# IC_74HC595.net
KiCad netlist of a schematic drawn in Altium Designer
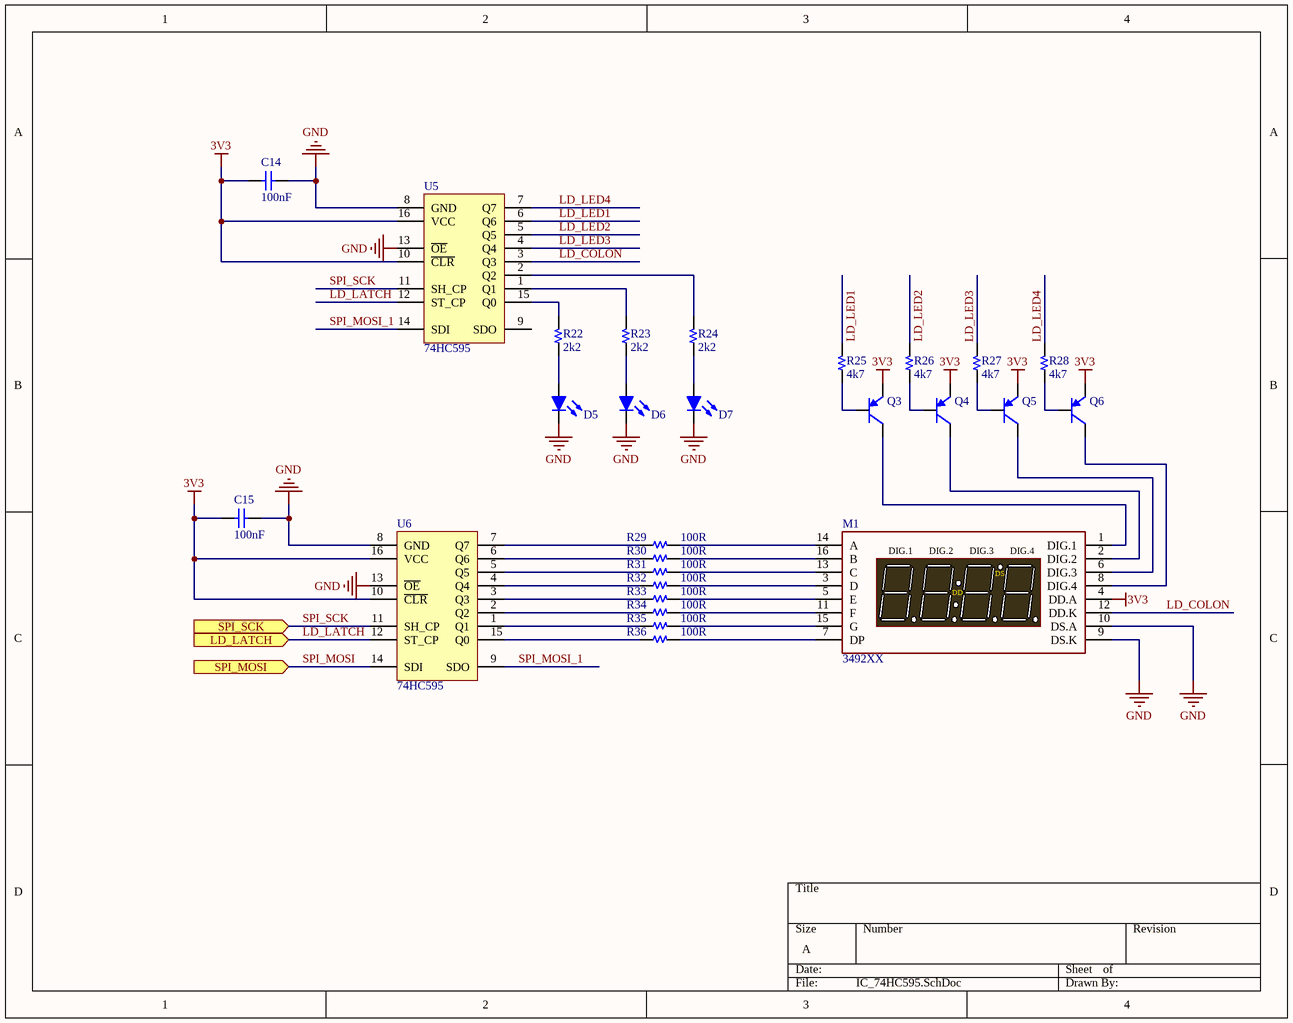
[diagram p0: IC_74HC595.SchDoc]

(export (version "E")
  (design (tool "Eeschema 10.0.6"))
  (components
    (comp (ref "C14")
      (value "100nF")
      (footprint "C 0805")
      (description "Capacitor non-pol")
      (libsource (lib "chipfc_altium_libs") (part "Capacitor NP"))
    )
    (comp (ref "C15")
      (value "100nF")
      (footprint "C 0805")
      (description "Capacitor non-pol")
      (libsource (lib "chipfc_altium_libs") (part "Capacitor NP"))
    )
    (comp (ref "D5")
      (value "Led")
      (footprint "Led 0805")
      (description "Typical LED")
      (libsource (lib "chipfc_altium_libs") (part "Led"))
    )
    (comp (ref "D6")
      (value "Led")
      (footprint "Led 0805")
      (description "Typical LED")
      (libsource (lib "chipfc_altium_libs") (part "Led"))
    )
    (comp (ref "D7")
      (value "Led")
      (footprint "Led 0805")
      (description "Typical LED")
      (libsource (lib "chipfc_altium_libs") (part "Led"))
    )
    (comp (ref "M1")
      (value "3492XX")
      (footprint "LED 7-SEG X4 3492XX")
      (description "LED 7-seg x4 HDSP-B09G")
      (libsource (lib "chipfc_altium_libs") (part "LED 7-SEG X4 3492"))
    )
    (comp (ref "Q3")
      (value "Transistor PNP")
      (footprint "SOT-23")
      (description "PNP Bipolar Transistor")
      (libsource (lib "chipfc_altium_libs") (part "Transistor PNP"))
    )
    (comp (ref "Q4")
      (value "Transistor PNP")
      (footprint "SOT-23")
      (description "PNP Bipolar Transistor")
      (libsource (lib "chipfc_altium_libs") (part "Transistor PNP"))
    )
    (comp (ref "Q5")
      (value "Transistor PNP")
      (footprint "SOT-23")
      (description "PNP Bipolar Transistor")
      (libsource (lib "chipfc_altium_libs") (part "Transistor PNP"))
    )
    (comp (ref "Q6")
      (value "Transistor PNP")
      (footprint "SOT-23")
      (description "PNP Bipolar Transistor")
      (libsource (lib "chipfc_altium_libs") (part "Transistor PNP"))
    )
    (comp (ref "R22")
      (value "2k2")
      (footprint "R 0805")
      (description "Resistor")
      (libsource (lib "chipfc_altium_libs") (part "Resistor"))
    )
    (comp (ref "R23")
      (value "2k2")
      (footprint "R 0805")
      (description "Resistor")
      (libsource (lib "chipfc_altium_libs") (part "Resistor"))
    )
    (comp (ref "R24")
      (value "2k2")
      (footprint "R 0805")
      (description "Resistor")
      (libsource (lib "chipfc_altium_libs") (part "Resistor"))
    )
    (comp (ref "R25")
      (value "4k7")
      (footprint "R 0805")
      (description "Resistor")
      (libsource (lib "chipfc_altium_libs") (part "Resistor"))
    )
    (comp (ref "R26")
      (value "4k7")
      (footprint "R 0805")
      (description "Resistor")
      (libsource (lib "chipfc_altium_libs") (part "Resistor"))
    )
    (comp (ref "R27")
      (value "4k7")
      (footprint "R 0805")
      (description "Resistor")
      (libsource (lib "chipfc_altium_libs") (part "Resistor"))
    )
    (comp (ref "R28")
      (value "4k7")
      (footprint "R 0805")
      (description "Resistor")
      (libsource (lib "chipfc_altium_libs") (part "Resistor"))
    )
    (comp (ref "R29")
      (value "100R")
      (footprint "R 0805")
      (description "Resistor")
      (libsource (lib "chipfc_altium_libs") (part "Resistor"))
    )
    (comp (ref "R30")
      (value "100R")
      (footprint "R 0805")
      (description "Resistor")
      (libsource (lib "chipfc_altium_libs") (part "Resistor"))
    )
    (comp (ref "R31")
      (value "100R")
      (footprint "R 0805")
      (description "Resistor")
      (libsource (lib "chipfc_altium_libs") (part "Resistor"))
    )
    (comp (ref "R32")
      (value "100R")
      (footprint "R 0805")
      (description "Resistor")
      (libsource (lib "chipfc_altium_libs") (part "Resistor"))
    )
    (comp (ref "R33")
      (value "100R")
      (footprint "R 0805")
      (description "Resistor")
      (libsource (lib "chipfc_altium_libs") (part "Resistor"))
    )
    (comp (ref "R34")
      (value "100R")
      (footprint "R 0805")
      (description "Resistor")
      (libsource (lib "chipfc_altium_libs") (part "Resistor"))
    )
    (comp (ref "R35")
      (value "100R")
      (footprint "R 0805")
      (description "Resistor")
      (libsource (lib "chipfc_altium_libs") (part "Resistor"))
    )
    (comp (ref "R36")
      (value "100R")
      (footprint "R 0805")
      (description "Resistor")
      (libsource (lib "chipfc_altium_libs") (part "Resistor"))
    )
    (comp (ref "U5")
      (value "74HC595")
      (footprint "SOIC-16")
      (description "8-bit serial-in, serial or parallel-out  shift register with output latches;  3-state")
      (libsource (lib "chipfc_altium_libs") (part "74HC595"))
    )
    (comp (ref "U6")
      (value "74HC595")
      (footprint "SOIC-16")
      (description "8-bit serial-in, serial or parallel-out  shift register with output latches;  3-state")
      (libsource (lib "chipfc_altium_libs") (part "74HC595"))
    )
  )
  (nets
    (net (code "1") (name "/LD_COLON") (class "Default")
      (node (ref "M1") (pin "12") (pinfunction "DD.K_12") (pintype "passive"))
      (node (ref "U5") (pin "3") (pinfunction "Q3_3") (pintype "passive"))
    )
    (net (code "2") (name "/LD_LATCH") (class "Default")
      (node (ref "U5") (pin "12") (pinfunction "ST_CP_12") (pintype "passive"))
      (node (ref "U6") (pin "12") (pinfunction "ST_CP_12") (pintype "passive"))
    )
    (net (code "3") (name "/LD_LED1") (class "Default")
      (node (ref "R25") (pin "2") (pinfunction "2_2") (pintype "passive"))
      (node (ref "U5") (pin "6") (pinfunction "Q6_6") (pintype "passive"))
    )
    (net (code "4") (name "/LD_LED2") (class "Default")
      (node (ref "R26") (pin "2") (pinfunction "2_2") (pintype "passive"))
      (node (ref "U5") (pin "5") (pinfunction "Q5_5") (pintype "passive"))
    )
    (net (code "5") (name "/LD_LED3") (class "Default")
      (node (ref "R27") (pin "2") (pinfunction "2_2") (pintype "passive"))
      (node (ref "U5") (pin "4") (pinfunction "Q4_4") (pintype "passive"))
    )
    (net (code "6") (name "/LD_LED4") (class "Default")
      (node (ref "R28") (pin "2") (pinfunction "2_2") (pintype "passive"))
      (node (ref "U5") (pin "7") (pinfunction "Q7_7") (pintype "passive"))
    )
    (net (code "7") (name "/SPI_MOSI") (class "Default")
      (node (ref "U6") (pin "14") (pinfunction "SDI_14") (pintype "passive"))
    )
    (net (code "8") (name "/SPI_MOSI_1") (class "Default")
      (node (ref "U5") (pin "14") (pinfunction "SDI_14") (pintype "passive"))
      (node (ref "U6") (pin "9") (pinfunction "SDO_9") (pintype "passive"))
    )
    (net (code "9") (name "/SPI_SCK") (class "Default")
      (node (ref "U5") (pin "11") (pinfunction "SH_CP_11") (pintype "passive"))
      (node (ref "U6") (pin "11") (pinfunction "SH_CP_11") (pintype "passive"))
    )
    (net (code "10") (name "3V3") (class "Default")
      (node (ref "C14") (pin "1") (pinfunction "1_1") (pintype "passive"))
      (node (ref "C15") (pin "1") (pinfunction "1_1") (pintype "passive"))
      (node (ref "M1") (pin "4") (pinfunction "DD.A_4") (pintype "passive"))
      (node (ref "Q3") (pin "2") (pinfunction "E_2") (pintype "passive"))
      (node (ref "Q4") (pin "2") (pinfunction "E_2") (pintype "passive"))
      (node (ref "Q5") (pin "2") (pinfunction "E_2") (pintype "passive"))
      (node (ref "Q6") (pin "2") (pinfunction "E_2") (pintype "passive"))
      (node (ref "U5") (pin "10") (pinfunction "~{CLR}_10") (pintype "passive"))
      (node (ref "U5") (pin "16") (pinfunction "VCC_16") (pintype "passive"))
      (node (ref "U6") (pin "10") (pinfunction "~{CLR}_10") (pintype "passive"))
      (node (ref "U6") (pin "16") (pinfunction "VCC_16") (pintype "passive"))
    )
    (net (code "11") (name "GND") (class "Default")
      (node (ref "C14") (pin "2") (pinfunction "2_2") (pintype "passive"))
      (node (ref "C15") (pin "2") (pinfunction "2_2") (pintype "passive"))
      (node (ref "D5") (pin "2") (pinfunction "K_2") (pintype "passive"))
      (node (ref "D6") (pin "2") (pinfunction "K_2") (pintype "passive"))
      (node (ref "D7") (pin "2") (pinfunction "K_2") (pintype "passive"))
      (node (ref "M1") (pin "10") (pinfunction "DS.A_10") (pintype "passive"))
      (node (ref "M1") (pin "9") (pinfunction "DS.K_9") (pintype "passive"))
      (node (ref "U5") (pin "13") (pinfunction "~{OE}_13") (pintype "passive"))
      (node (ref "U5") (pin "8") (pinfunction "GND_8") (pintype "passive"))
      (node (ref "U6") (pin "13") (pinfunction "~{OE}_13") (pintype "passive"))
      (node (ref "U6") (pin "8") (pinfunction "GND_8") (pintype "passive"))
    )
    (net (code "12") (name "Net-(D5-A)") (class "Default")
      (node (ref "D5") (pin "1") (pinfunction "A_1") (pintype "passive"))
      (node (ref "R22") (pin "1") (pinfunction "1_1") (pintype "passive"))
    )
    (net (code "13") (name "Net-(D6-A)") (class "Default")
      (node (ref "D6") (pin "1") (pinfunction "A_1") (pintype "passive"))
      (node (ref "R23") (pin "1") (pinfunction "1_1") (pintype "passive"))
    )
    (net (code "14") (name "Net-(D7-A)") (class "Default")
      (node (ref "D7") (pin "1") (pinfunction "A_1") (pintype "passive"))
      (node (ref "R24") (pin "1") (pinfunction "1_1") (pintype "passive"))
    )
    (net (code "15") (name "Net-(M1-A)") (class "Default")
      (node (ref "M1") (pin "14") (pinfunction "A_14") (pintype "passive"))
      (node (ref "R29") (pin "2") (pinfunction "2_2") (pintype "passive"))
    )
    (net (code "16") (name "Net-(M1-B)") (class "Default")
      (node (ref "M1") (pin "16") (pinfunction "B_16") (pintype "passive"))
      (node (ref "R30") (pin "2") (pinfunction "2_2") (pintype "passive"))
    )
    (net (code "17") (name "Net-(M1-C)") (class "Default")
      (node (ref "M1") (pin "13") (pinfunction "C_13") (pintype "passive"))
      (node (ref "R31") (pin "2") (pinfunction "2_2") (pintype "passive"))
    )
    (net (code "18") (name "Net-(M1-D)") (class "Default")
      (node (ref "M1") (pin "3") (pinfunction "D_3") (pintype "passive"))
      (node (ref "R32") (pin "2") (pinfunction "2_2") (pintype "passive"))
    )
    (net (code "19") (name "Net-(M1-DIG.1)") (class "Default")
      (node (ref "M1") (pin "1") (pinfunction "DIG.1_1") (pintype "passive"))
      (node (ref "Q3") (pin "3") (pinfunction "C_3") (pintype "passive"))
    )
    (net (code "20") (name "Net-(M1-DIG.2)") (class "Default")
      (node (ref "M1") (pin "2") (pinfunction "DIG.2_2") (pintype "passive"))
      (node (ref "Q4") (pin "3") (pinfunction "C_3") (pintype "passive"))
    )
    (net (code "21") (name "Net-(M1-DIG.3)") (class "Default")
      (node (ref "M1") (pin "6") (pinfunction "DIG.3_6") (pintype "passive"))
      (node (ref "Q5") (pin "3") (pinfunction "C_3") (pintype "passive"))
    )
    (net (code "22") (name "Net-(M1-DIG.4)") (class "Default")
      (node (ref "M1") (pin "8") (pinfunction "DIG.4_8") (pintype "passive"))
      (node (ref "Q6") (pin "3") (pinfunction "C_3") (pintype "passive"))
    )
    (net (code "23") (name "Net-(M1-DP)") (class "Default")
      (node (ref "M1") (pin "7") (pinfunction "DP_7") (pintype "passive"))
      (node (ref "R36") (pin "2") (pinfunction "2_2") (pintype "passive"))
    )
    (net (code "24") (name "Net-(M1-E)") (class "Default")
      (node (ref "M1") (pin "5") (pinfunction "E_5") (pintype "passive"))
      (node (ref "R33") (pin "2") (pinfunction "2_2") (pintype "passive"))
    )
    (net (code "25") (name "Net-(M1-F)") (class "Default")
      (node (ref "M1") (pin "11") (pinfunction "F_11") (pintype "passive"))
      (node (ref "R34") (pin "2") (pinfunction "2_2") (pintype "passive"))
    )
    (net (code "26") (name "Net-(M1-G)") (class "Default")
      (node (ref "M1") (pin "15") (pinfunction "G_15") (pintype "passive"))
      (node (ref "R35") (pin "2") (pinfunction "2_2") (pintype "passive"))
    )
    (net (code "27") (name "Net-(Q3-B)") (class "Default")
      (node (ref "Q3") (pin "1") (pinfunction "B_1") (pintype "passive"))
      (node (ref "R25") (pin "1") (pinfunction "1_1") (pintype "passive"))
    )
    (net (code "28") (name "Net-(Q4-B)") (class "Default")
      (node (ref "Q4") (pin "1") (pinfunction "B_1") (pintype "passive"))
      (node (ref "R26") (pin "1") (pinfunction "1_1") (pintype "passive"))
    )
    (net (code "29") (name "Net-(Q5-B)") (class "Default")
      (node (ref "Q5") (pin "1") (pinfunction "B_1") (pintype "passive"))
      (node (ref "R27") (pin "1") (pinfunction "1_1") (pintype "passive"))
    )
    (net (code "30") (name "Net-(Q6-B)") (class "Default")
      (node (ref "Q6") (pin "1") (pinfunction "B_1") (pintype "passive"))
      (node (ref "R28") (pin "1") (pinfunction "1_1") (pintype "passive"))
    )
    (net (code "31") (name "Net-(U5-Q0)") (class "Default")
      (node (ref "R22") (pin "2") (pinfunction "2_2") (pintype "passive"))
      (node (ref "U5") (pin "15") (pinfunction "Q0_15") (pintype "passive"))
    )
    (net (code "32") (name "Net-(U5-Q1)") (class "Default")
      (node (ref "R23") (pin "2") (pinfunction "2_2") (pintype "passive"))
      (node (ref "U5") (pin "1") (pinfunction "Q1_1") (pintype "passive"))
    )
    (net (code "33") (name "Net-(U5-Q2)") (class "Default")
      (node (ref "R24") (pin "2") (pinfunction "2_2") (pintype "passive"))
      (node (ref "U5") (pin "2") (pinfunction "Q2_2") (pintype "passive"))
    )
    (net (code "34") (name "Net-(U6-Q0)") (class "Default")
      (node (ref "R36") (pin "1") (pinfunction "1_1") (pintype "passive"))
      (node (ref "U6") (pin "15") (pinfunction "Q0_15") (pintype "passive"))
    )
    (net (code "35") (name "Net-(U6-Q1)") (class "Default")
      (node (ref "R35") (pin "1") (pinfunction "1_1") (pintype "passive"))
      (node (ref "U6") (pin "1") (pinfunction "Q1_1") (pintype "passive"))
    )
    (net (code "36") (name "Net-(U6-Q2)") (class "Default")
      (node (ref "R34") (pin "1") (pinfunction "1_1") (pintype "passive"))
      (node (ref "U6") (pin "2") (pinfunction "Q2_2") (pintype "passive"))
    )
    (net (code "37") (name "Net-(U6-Q3)") (class "Default")
      (node (ref "R33") (pin "1") (pinfunction "1_1") (pintype "passive"))
      (node (ref "U6") (pin "3") (pinfunction "Q3_3") (pintype "passive"))
    )
    (net (code "38") (name "Net-(U6-Q4)") (class "Default")
      (node (ref "R32") (pin "1") (pinfunction "1_1") (pintype "passive"))
      (node (ref "U6") (pin "4") (pinfunction "Q4_4") (pintype "passive"))
    )
    (net (code "39") (name "Net-(U6-Q5)") (class "Default")
      (node (ref "R31") (pin "1") (pinfunction "1_1") (pintype "passive"))
      (node (ref "U6") (pin "5") (pinfunction "Q5_5") (pintype "passive"))
    )
    (net (code "40") (name "Net-(U6-Q6)") (class "Default")
      (node (ref "R30") (pin "1") (pinfunction "1_1") (pintype "passive"))
      (node (ref "U6") (pin "6") (pinfunction "Q6_6") (pintype "passive"))
    )
    (net (code "41") (name "Net-(U6-Q7)") (class "Default")
      (node (ref "R29") (pin "1") (pinfunction "1_1") (pintype "passive"))
      (node (ref "U6") (pin "7") (pinfunction "Q7_7") (pintype "passive"))
    )
    (net (code "42") (name "unconnected-(U5-SDO-Pad9)") (class "Default")
      (node (ref "U5") (pin "9") (pinfunction "SDO_9") (pintype "passive"))
    )
  )
)
